# MM6108IQ_Chip.net
KiCad netlist of a schematic drawn in Altium Designer
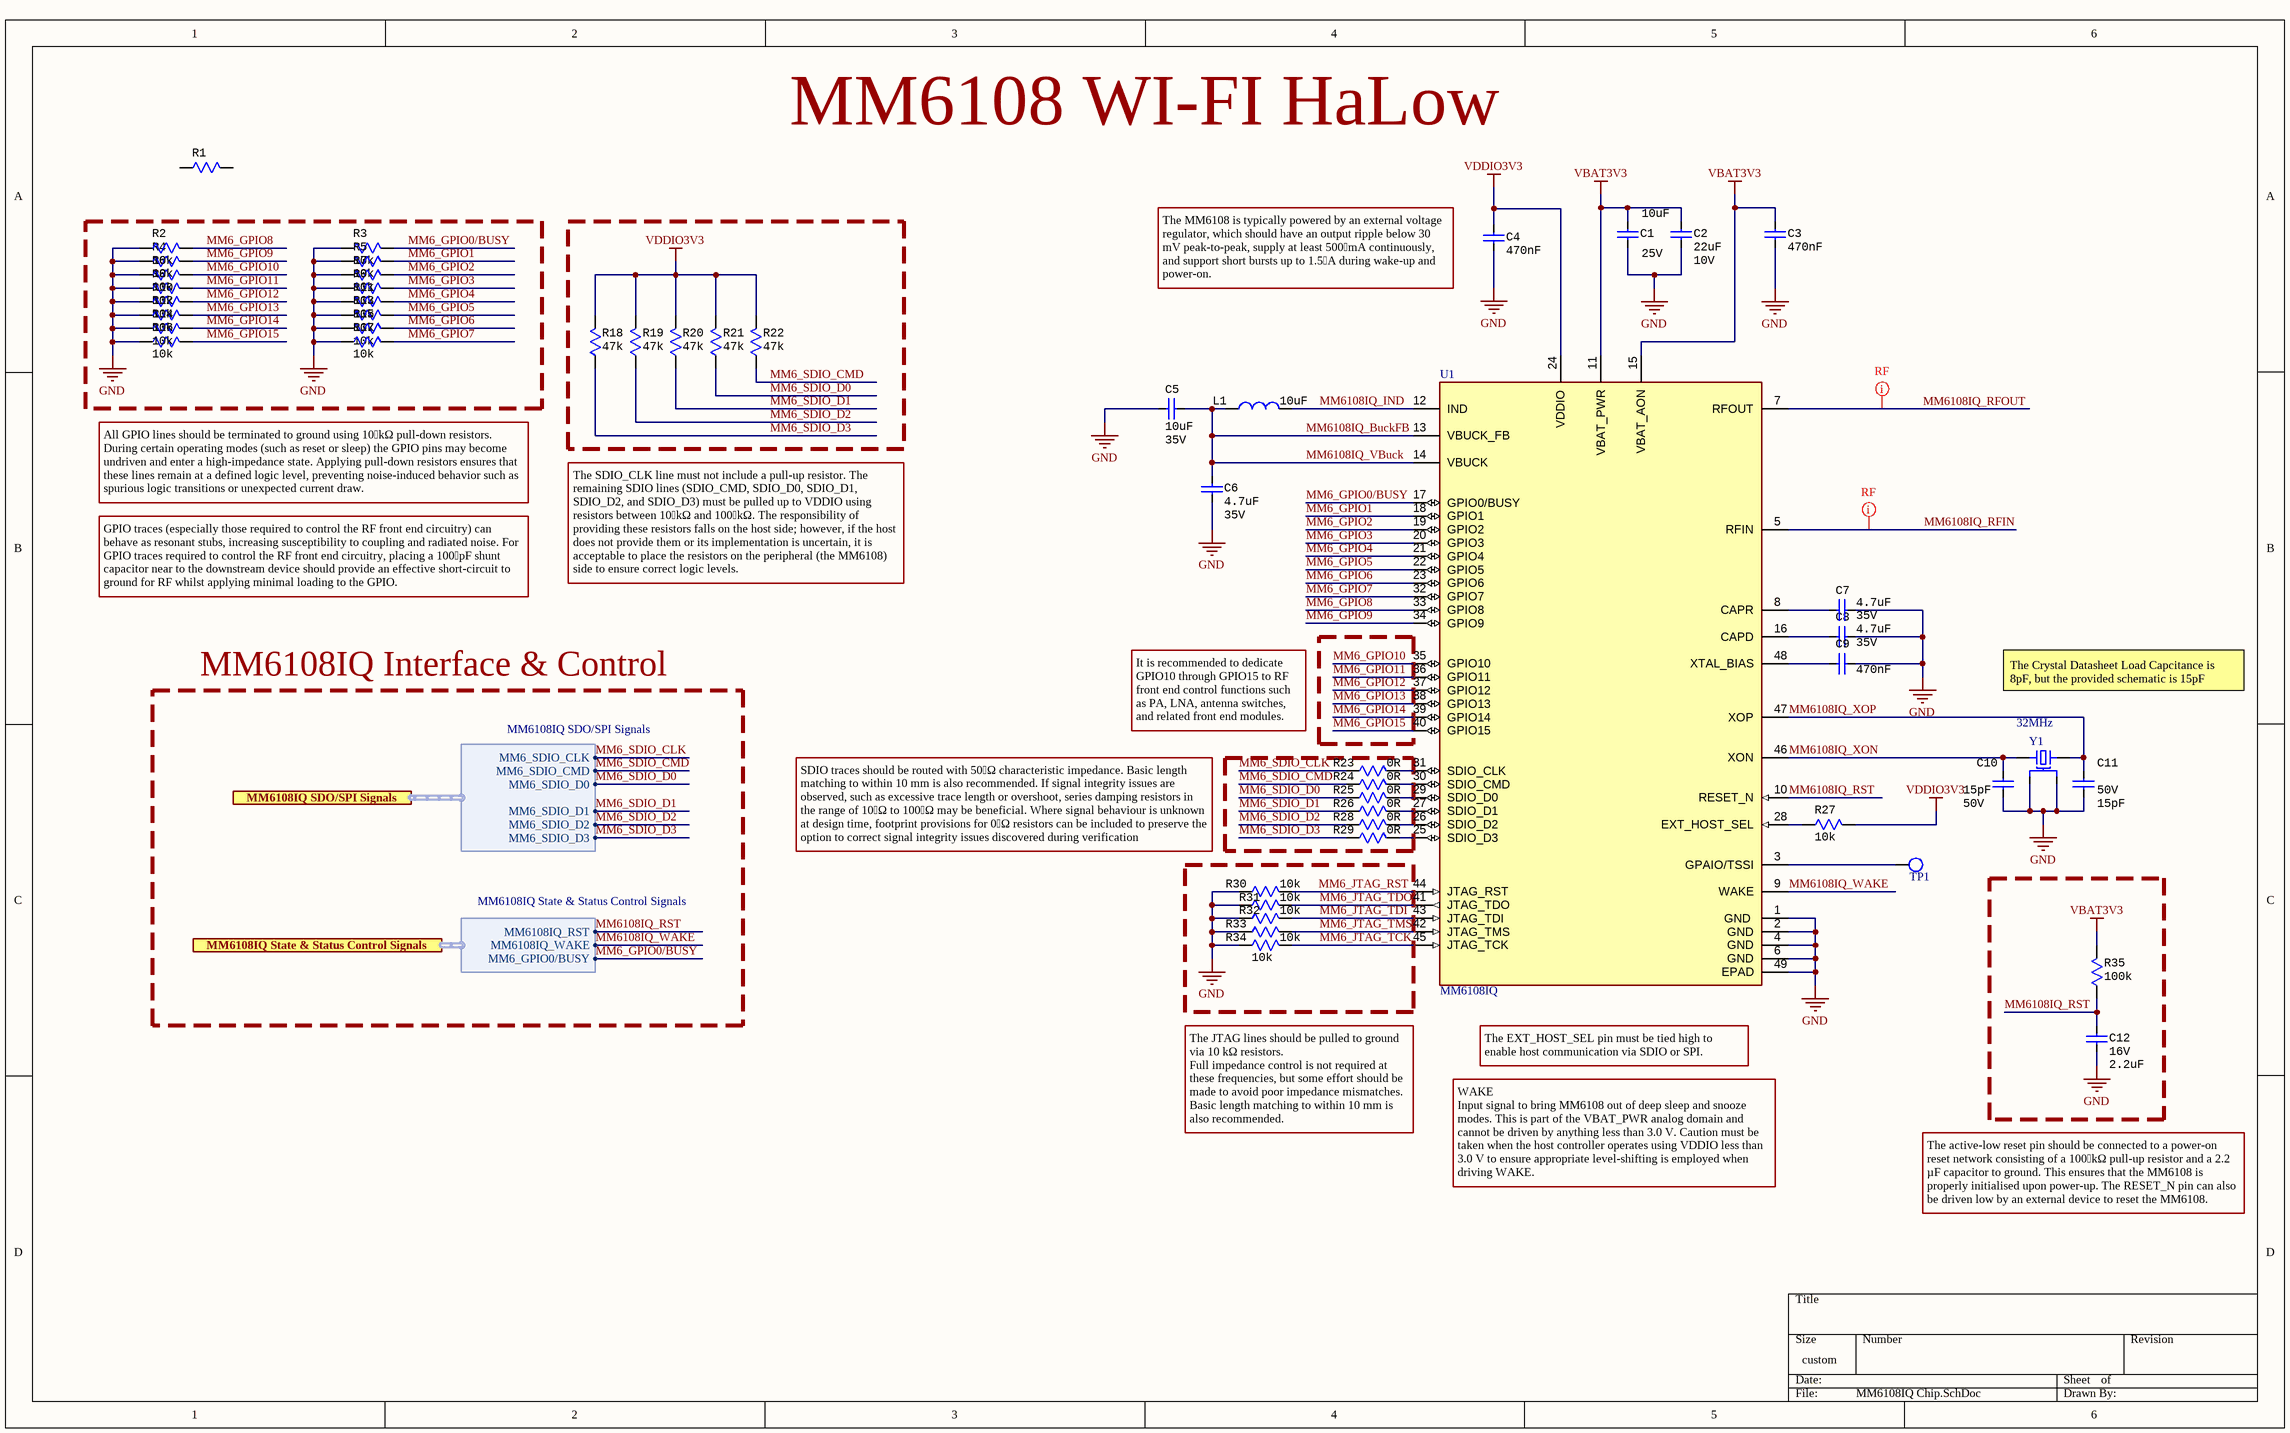
[diagram p0: MM6108IQ Chip.SchDoc]

(export (version "E")
  (design (tool "Eeschema 10.0.6"))
  (components
    (comp (ref "C1")
      (value "10uF")
      (footprint "CAP Ceramic SMD 0805")
      (description "CAP CER 10uF 25V X7R 0805")
      (fields
        (field (name "MANUFACTURER") "Samsung Electro-Mechanics")
        (field (name "MANUFACTURER PART NUMBER") "CL21B106KAYQNNE")
        (field (name "VOLTAGE") "25V")
      )
      (libsource (lib "MM6108IQ MotherBoard") (part "CAP 0805 10uF 25V 10%"))
    )
    (comp (ref "C2")
      (value "22uF")
      (footprint "CAP Ceramic SMD 0805")
      (description "CAP CER 22uF 10V X7R 0805")
      (fields
        (field (name "MANUFACTURER") "muRata")
        (field (name "MANUFACTURER PART NUMBER") "GRM21BZ71A226ME15L")
        (field (name "VOLTAGE") "10V")
      )
      (libsource (lib "MM6108IQ MotherBoard") (part "CAP 0805 22uF 10V"))
    )
    (comp (ref "C3")
      (value "470nF")
      (footprint "CAP Ceramic SMD 0603")
      (description "470nF ±10% 25V Ceramic Capacitor X7R 0603")
      (fields
        (field (name "MANUFACTURER") "Samsung Electro-Mechanics")
        (field (name "MANUFACTURER PART NUMBER") "CL10B474KA8NNNC")
      )
      (libsource (lib "MM6108IQ MotherBoard") (part "CAP 0603 470nF 25V"))
    )
    (comp (ref "C4")
      (value "470nF")
      (footprint "CAP Ceramic SMD 0603")
      (description "470nF ±10% 25V Ceramic Capacitor X7R 0603")
      (fields
        (field (name "MANUFACTURER") "Samsung Electro-Mechanics")
        (field (name "MANUFACTURER PART NUMBER") "CL10B474KA8NNNC")
      )
      (libsource (lib "MM6108IQ MotherBoard") (part "CAP 0603 470nF 25V"))
    )
    (comp (ref "C5")
      (value "10uF")
      (footprint "CAP Ceramic SMD 0603")
      (description "Cap Ceramic 10uF 35V X5R 20% Pad SMD 0603 85C T/R")
      (fields
        (field (name "MANUFACTURER") "Murata")
        (field (name "MANUFACTURER PART NUMBER") "GRM188R6YA106MA73D")
        (field (name "VOLTAGE") "35V")
      )
      (libsource (lib "MM6108IQ MotherBoard") (part "CAP 0603 10uF 35V"))
    )
    (comp (ref "C6")
      (value "4.7uF")
      (footprint "CAP Ceramic SMD 0603")
      (description "25V 4.7uF X5R ±10% 0603 Multilayer Ceramic Capacitors MLCC - SMD/SMT ROHS")
      (fields
        (field (name "MANUFACTURER") "Samsung Electro-Mechanics")
        (field (name "MANUFACTURER PART NUMBER") "CL10A475KA8NQNC")
        (field (name "VOLTAGE") "35V")
      )
      (libsource (lib "MM6108IQ MotherBoard") (part "CAP 0603 4.7uF 25V X5R 10%"))
    )
    (comp (ref "C7")
      (value "4.7uF")
      (footprint "CAP Ceramic SMD 0603")
      (description "25V 4.7uF X5R ±10% 0603 Multilayer Ceramic Capacitors MLCC - SMD/SMT ROHS")
      (fields
        (field (name "MANUFACTURER") "Samsung Electro-Mechanics")
        (field (name "MANUFACTURER PART NUMBER") "CL10A475KA8NQNC")
        (field (name "VOLTAGE") "35V")
      )
      (libsource (lib "MM6108IQ MotherBoard") (part "CAP 0603 4.7uF 25V X5R 10%"))
    )
    (comp (ref "C8")
      (value "4.7uF")
      (footprint "CAP Ceramic SMD 0603")
      (description "25V 4.7uF X5R ±10% 0603 Multilayer Ceramic Capacitors MLCC - SMD/SMT ROHS")
      (fields
        (field (name "MANUFACTURER") "Samsung Electro-Mechanics")
        (field (name "MANUFACTURER PART NUMBER") "CL10A475KA8NQNC")
        (field (name "VOLTAGE") "35V")
      )
      (libsource (lib "MM6108IQ MotherBoard") (part "CAP 0603 4.7uF 25V X5R 10%"))
    )
    (comp (ref "C9")
      (value "470nF")
      (footprint "CAP Ceramic SMD 0603")
      (description "470nF ±10% 25V Ceramic Capacitor X7R 0603")
      (fields
        (field (name "MANUFACTURER") "Samsung Electro-Mechanics")
        (field (name "MANUFACTURER PART NUMBER") "CL10B474KA8NNNC")
      )
      (libsource (lib "MM6108IQ MotherBoard") (part "CAP 0603 470nF 25V"))
    )
    (comp (ref "C10")
      (value "15pF")
      (footprint "CAP Ceramic SMD 0603")
      (description "50V 15pF NP0 ±5% 0603 Multilayer Ceramic Capacitors MLCC - SMD/SMT ROHS")
      (fields
        (field (name "MANUFACTURER") "Yageo")
        (field (name "MANUFACTURER PART NUMBER") "CC0603JRNPO9BN150")
        (field (name "VOLTAGE") "50V")
      )
      (libsource (lib "MM6108IQ MotherBoard") (part "CAP 0603 15pF 50V NP0 5%"))
    )
    (comp (ref "C11")
      (value "15pF")
      (footprint "CAP Ceramic SMD 0603")
      (description "50V 15pF NP0 ±5% 0603 Multilayer Ceramic Capacitors MLCC - SMD/SMT ROHS")
      (fields
        (field (name "MANUFACTURER") "Yageo")
        (field (name "MANUFACTURER PART NUMBER") "CC0603JRNPO9BN150")
        (field (name "VOLTAGE") "50V")
      )
      (libsource (lib "MM6108IQ MotherBoard") (part "CAP 0603 15pF 50V NP0 5%"))
    )
    (comp (ref "C12")
      (value "2.2uF")
      (footprint "CAP Ceramic SMD 0603")
      (description "16V 2.2uF X5R ±10% 0603 Multilayer Ceramic Capacitors MLCC - SMD/SMT ROHS")
      (fields
        (field (name "MANUFACTURER") "YAGEO")
        (field (name "MANUFACTURER PART NUMBER") "CC0603KRX5R7BB225")
        (field (name "VOLTAGE") "16V")
        (field (name "CAPACITANCE") "2.2uF")
      )
      (libsource (lib "MM6108IQ MotherBoard") (part "CAP 0603 2.2uF 16V"))
    )
    (comp (ref "L1")
      (value "10uF")
      (footprint "IND SMD 1210")
      (description "FIXED IND 10uH 2.2A 210mΩ 1210")
      (fields
        (field (name "MANUFACTURER") "XR")
        (field (name "MANUFACTURER PART NUMBER") "XRTC322512S100MBCA")
      )
      (libsource (lib "MM6108IQ MotherBoard") (part "IND 1210 10uF 20% 2.2A"))
    )
    (comp (ref "R1")
      (value "~")
      (footprint "RES SMD 0603")
      (description "100mW Thick Film Resistors 75V ±100ppm/℃ ±1% 10kΩ 0603 Chip Resistor - Surface Mount ROHS")
      (fields
        (field (name "MANUFACTURER") "YAGEO")
        (field (name "MANUFACTURER PART NUMBER") "RC0603FR-0710KL")
      )
      (libsource (lib "MM6108IQ MotherBoard") (part "RES 0603 10k 1%"))
    )
    (comp (ref "R2")
      (value "10k")
      (footprint "RES SMD 0603")
      (description "100mW Thick Film Resistors 75V ±100ppm/℃ ±1% 10kΩ 0603 Chip Resistor - Surface Mount ROHS")
      (fields
        (field (name "MANUFACTURER") "YAGEO")
        (field (name "MANUFACTURER PART NUMBER") "RC0603FR-0710KL")
      )
      (libsource (lib "MM6108IQ MotherBoard") (part "RES 0603 10k 1%"))
    )
    (comp (ref "R3")
      (value "10k")
      (footprint "RES SMD 0603")
      (description "100mW Thick Film Resistors 75V ±100ppm/℃ ±1% 10kΩ 0603 Chip Resistor - Surface Mount ROHS")
      (fields
        (field (name "MANUFACTURER") "YAGEO")
        (field (name "MANUFACTURER PART NUMBER") "RC0603FR-0710KL")
      )
      (libsource (lib "MM6108IQ MotherBoard") (part "RES 0603 10k 1%"))
    )
    (comp (ref "R4")
      (value "10k")
      (footprint "RES SMD 0603")
      (description "100mW Thick Film Resistors 75V ±100ppm/℃ ±1% 10kΩ 0603 Chip Resistor - Surface Mount ROHS")
      (fields
        (field (name "MANUFACTURER") "YAGEO")
        (field (name "MANUFACTURER PART NUMBER") "RC0603FR-0710KL")
      )
      (libsource (lib "MM6108IQ MotherBoard") (part "RES 0603 10k 1%"))
    )
    (comp (ref "R5")
      (value "10k")
      (footprint "RES SMD 0603")
      (description "100mW Thick Film Resistors 75V ±100ppm/℃ ±1% 10kΩ 0603 Chip Resistor - Surface Mount ROHS")
      (fields
        (field (name "MANUFACTURER") "YAGEO")
        (field (name "MANUFACTURER PART NUMBER") "RC0603FR-0710KL")
      )
      (libsource (lib "MM6108IQ MotherBoard") (part "RES 0603 10k 1%"))
    )
    (comp (ref "R6")
      (value "10k")
      (footprint "RES SMD 0603")
      (description "100mW Thick Film Resistors 75V ±100ppm/℃ ±1% 10kΩ 0603 Chip Resistor - Surface Mount ROHS")
      (fields
        (field (name "MANUFACTURER") "YAGEO")
        (field (name "MANUFACTURER PART NUMBER") "RC0603FR-0710KL")
      )
      (libsource (lib "MM6108IQ MotherBoard") (part "RES 0603 10k 1%"))
    )
    (comp (ref "R7")
      (value "10k")
      (footprint "RES SMD 0603")
      (description "100mW Thick Film Resistors 75V ±100ppm/℃ ±1% 10kΩ 0603 Chip Resistor - Surface Mount ROHS")
      (fields
        (field (name "MANUFACTURER") "YAGEO")
        (field (name "MANUFACTURER PART NUMBER") "RC0603FR-0710KL")
      )
      (libsource (lib "MM6108IQ MotherBoard") (part "RES 0603 10k 1%"))
    )
    (comp (ref "R8")
      (value "10k")
      (footprint "RES SMD 0603")
      (description "100mW Thick Film Resistors 75V ±100ppm/℃ ±1% 10kΩ 0603 Chip Resistor - Surface Mount ROHS")
      (fields
        (field (name "MANUFACTURER") "YAGEO")
        (field (name "MANUFACTURER PART NUMBER") "RC0603FR-0710KL")
      )
      (libsource (lib "MM6108IQ MotherBoard") (part "RES 0603 10k 1%"))
    )
    (comp (ref "R9")
      (value "10k")
      (footprint "RES SMD 0603")
      (description "100mW Thick Film Resistors 75V ±100ppm/℃ ±1% 10kΩ 0603 Chip Resistor - Surface Mount ROHS")
      (fields
        (field (name "MANUFACTURER") "YAGEO")
        (field (name "MANUFACTURER PART NUMBER") "RC0603FR-0710KL")
      )
      (libsource (lib "MM6108IQ MotherBoard") (part "RES 0603 10k 1%"))
    )
    (comp (ref "R10")
      (value "10k")
      (footprint "RES SMD 0603")
      (description "100mW Thick Film Resistors 75V ±100ppm/℃ ±1% 10kΩ 0603 Chip Resistor - Surface Mount ROHS")
      (fields
        (field (name "MANUFACTURER") "YAGEO")
        (field (name "MANUFACTURER PART NUMBER") "RC0603FR-0710KL")
      )
      (libsource (lib "MM6108IQ MotherBoard") (part "RES 0603 10k 1%"))
    )
    (comp (ref "R11")
      (value "10k")
      (footprint "RES SMD 0603")
      (description "100mW Thick Film Resistors 75V ±100ppm/℃ ±1% 10kΩ 0603 Chip Resistor - Surface Mount ROHS")
      (fields
        (field (name "MANUFACTURER") "YAGEO")
        (field (name "MANUFACTURER PART NUMBER") "RC0603FR-0710KL")
      )
      (libsource (lib "MM6108IQ MotherBoard") (part "RES 0603 10k 1%"))
    )
    (comp (ref "R12")
      (value "10k")
      (footprint "RES SMD 0603")
      (description "100mW Thick Film Resistors 75V ±100ppm/℃ ±1% 10kΩ 0603 Chip Resistor - Surface Mount ROHS")
      (fields
        (field (name "MANUFACTURER") "YAGEO")
        (field (name "MANUFACTURER PART NUMBER") "RC0603FR-0710KL")
      )
      (libsource (lib "MM6108IQ MotherBoard") (part "RES 0603 10k 1%"))
    )
    (comp (ref "R13")
      (value "10k")
      (footprint "RES SMD 0603")
      (description "100mW Thick Film Resistors 75V ±100ppm/℃ ±1% 10kΩ 0603 Chip Resistor - Surface Mount ROHS")
      (fields
        (field (name "MANUFACTURER") "YAGEO")
        (field (name "MANUFACTURER PART NUMBER") "RC0603FR-0710KL")
      )
      (libsource (lib "MM6108IQ MotherBoard") (part "RES 0603 10k 1%"))
    )
    (comp (ref "R14")
      (value "10k")
      (footprint "RES SMD 0603")
      (description "100mW Thick Film Resistors 75V ±100ppm/℃ ±1% 10kΩ 0603 Chip Resistor - Surface Mount ROHS")
      (fields
        (field (name "MANUFACTURER") "YAGEO")
        (field (name "MANUFACTURER PART NUMBER") "RC0603FR-0710KL")
      )
      (libsource (lib "MM6108IQ MotherBoard") (part "RES 0603 10k 1%"))
    )
    (comp (ref "R15")
      (value "10k")
      (footprint "RES SMD 0603")
      (description "100mW Thick Film Resistors 75V ±100ppm/℃ ±1% 10kΩ 0603 Chip Resistor - Surface Mount ROHS")
      (fields
        (field (name "MANUFACTURER") "YAGEO")
        (field (name "MANUFACTURER PART NUMBER") "RC0603FR-0710KL")
      )
      (libsource (lib "MM6108IQ MotherBoard") (part "RES 0603 10k 1%"))
    )
    (comp (ref "R16")
      (value "10k")
      (footprint "RES SMD 0603")
      (description "100mW Thick Film Resistors 75V ±100ppm/℃ ±1% 10kΩ 0603 Chip Resistor - Surface Mount ROHS")
      (fields
        (field (name "MANUFACTURER") "YAGEO")
        (field (name "MANUFACTURER PART NUMBER") "RC0603FR-0710KL")
      )
      (libsource (lib "MM6108IQ MotherBoard") (part "RES 0603 10k 1%"))
    )
    (comp (ref "R17")
      (value "10k")
      (footprint "RES SMD 0603")
      (description "100mW Thick Film Resistors 75V ±100ppm/℃ ±1% 10kΩ 0603 Chip Resistor - Surface Mount ROHS")
      (fields
        (field (name "MANUFACTURER") "YAGEO")
        (field (name "MANUFACTURER PART NUMBER") "RC0603FR-0710KL")
      )
      (libsource (lib "MM6108IQ MotherBoard") (part "RES 0603 10k 1%"))
    )
    (comp (ref "R18")
      (value "47k")
      (footprint "RES SMD 0603")
      (description "Res Thick Film 0603 47K Ohm 1% 1/10W ±100ppm/°C Molded SMD Punched Carrier T/R")
      (fields
        (field (name "MANUFACTURER") "YAGEO")
        (field (name "MANUFACTURER PART NUMBER") "RC0603FR-0747KL")
      )
      (libsource (lib "MM6108IQ MotherBoard") (part "RES 0603 47k 1%"))
    )
    (comp (ref "R19")
      (value "47k")
      (footprint "RES SMD 0603")
      (description "Res Thick Film 0603 47K Ohm 1% 1/10W ±100ppm/°C Molded SMD Punched Carrier T/R")
      (fields
        (field (name "MANUFACTURER") "YAGEO")
        (field (name "MANUFACTURER PART NUMBER") "RC0603FR-0747KL")
      )
      (libsource (lib "MM6108IQ MotherBoard") (part "RES 0603 47k 1%"))
    )
    (comp (ref "R20")
      (value "47k")
      (footprint "RES SMD 0603")
      (description "Res Thick Film 0603 47K Ohm 1% 1/10W ±100ppm/°C Molded SMD Punched Carrier T/R")
      (fields
        (field (name "MANUFACTURER") "YAGEO")
        (field (name "MANUFACTURER PART NUMBER") "RC0603FR-0747KL")
      )
      (libsource (lib "MM6108IQ MotherBoard") (part "RES 0603 47k 1%"))
    )
    (comp (ref "R21")
      (value "47k")
      (footprint "RES SMD 0603")
      (description "Res Thick Film 0603 47K Ohm 1% 1/10W ±100ppm/°C Molded SMD Punched Carrier T/R")
      (fields
        (field (name "MANUFACTURER") "YAGEO")
        (field (name "MANUFACTURER PART NUMBER") "RC0603FR-0747KL")
      )
      (libsource (lib "MM6108IQ MotherBoard") (part "RES 0603 47k 1%"))
    )
    (comp (ref "R22")
      (value "47k")
      (footprint "RES SMD 0603")
      (description "Res Thick Film 0603 47K Ohm 1% 1/10W ±100ppm/°C Molded SMD Punched Carrier T/R")
      (fields
        (field (name "MANUFACTURER") "YAGEO")
        (field (name "MANUFACTURER PART NUMBER") "RC0603FR-0747KL")
      )
      (libsource (lib "MM6108IQ MotherBoard") (part "RES 0603 47k 1%"))
    )
    (comp (ref "R23")
      (value "0R")
      (footprint "RES SMD 0603")
      (description "100mW Thick Film Resistors 75V ±5% 0Ω 0603 Chip Resistor - Surface Mount ROHS")
      (fields
        (field (name "MANUFACTURER") "YAGEO")
        (field (name "MANUFACTURER PART NUMBER") "RC0603JR-070RL")
      )
      (libsource (lib "MM6108IQ MotherBoard") (part "RES 0603 0R 1%"))
    )
    (comp (ref "R24")
      (value "0R")
      (footprint "RES SMD 0603")
      (description "100mW Thick Film Resistors 75V ±5% 0Ω 0603 Chip Resistor - Surface Mount ROHS")
      (fields
        (field (name "MANUFACTURER") "YAGEO")
        (field (name "MANUFACTURER PART NUMBER") "RC0603JR-070RL")
      )
      (libsource (lib "MM6108IQ MotherBoard") (part "RES 0603 0R 1%"))
    )
    (comp (ref "R25")
      (value "0R")
      (footprint "RES SMD 0603")
      (description "100mW Thick Film Resistors 75V ±5% 0Ω 0603 Chip Resistor - Surface Mount ROHS")
      (fields
        (field (name "MANUFACTURER") "YAGEO")
        (field (name "MANUFACTURER PART NUMBER") "RC0603JR-070RL")
      )
      (libsource (lib "MM6108IQ MotherBoard") (part "RES 0603 0R 1%"))
    )
    (comp (ref "R26")
      (value "0R")
      (footprint "RES SMD 0603")
      (description "100mW Thick Film Resistors 75V ±5% 0Ω 0603 Chip Resistor - Surface Mount ROHS")
      (fields
        (field (name "MANUFACTURER") "YAGEO")
        (field (name "MANUFACTURER PART NUMBER") "RC0603JR-070RL")
      )
      (libsource (lib "MM6108IQ MotherBoard") (part "RES 0603 0R 1%"))
    )
    (comp (ref "R27")
      (value "10k")
      (footprint "RES SMD 0603")
      (description "100mW Thick Film Resistors 75V ±100ppm/℃ ±1% 10kΩ 0603 Chip Resistor - Surface Mount ROHS")
      (fields
        (field (name "MANUFACTURER") "YAGEO")
        (field (name "MANUFACTURER PART NUMBER") "RC0603FR-0710KL")
      )
      (libsource (lib "MM6108IQ MotherBoard") (part "RES 0603 10k 1%"))
    )
    (comp (ref "R28")
      (value "0R")
      (footprint "RES SMD 0603")
      (description "100mW Thick Film Resistors 75V ±5% 0Ω 0603 Chip Resistor - Surface Mount ROHS")
      (fields
        (field (name "MANUFACTURER") "YAGEO")
        (field (name "MANUFACTURER PART NUMBER") "RC0603JR-070RL")
      )
      (libsource (lib "MM6108IQ MotherBoard") (part "RES 0603 0R 1%"))
    )
    (comp (ref "R29")
      (value "0R")
      (footprint "RES SMD 0603")
      (description "100mW Thick Film Resistors 75V ±5% 0Ω 0603 Chip Resistor - Surface Mount ROHS")
      (fields
        (field (name "MANUFACTURER") "YAGEO")
        (field (name "MANUFACTURER PART NUMBER") "RC0603JR-070RL")
      )
      (libsource (lib "MM6108IQ MotherBoard") (part "RES 0603 0R 1%"))
    )
    (comp (ref "R30")
      (value "10k")
      (footprint "RES SMD 0603")
      (description "100mW Thick Film Resistors 75V ±100ppm/℃ ±1% 10kΩ 0603 Chip Resistor - Surface Mount ROHS")
      (fields
        (field (name "MANUFACTURER") "YAGEO")
        (field (name "MANUFACTURER PART NUMBER") "RC0603FR-0710KL")
      )
      (libsource (lib "MM6108IQ MotherBoard") (part "RES 0603 10k 1%"))
    )
    (comp (ref "R31")
      (value "10k")
      (footprint "RES SMD 0603")
      (description "100mW Thick Film Resistors 75V ±100ppm/℃ ±1% 10kΩ 0603 Chip Resistor - Surface Mount ROHS")
      (fields
        (field (name "MANUFACTURER") "YAGEO")
        (field (name "MANUFACTURER PART NUMBER") "RC0603FR-0710KL")
      )
      (libsource (lib "MM6108IQ MotherBoard") (part "RES 0603 10k 1%"))
    )
    (comp (ref "R32")
      (value "10k")
      (footprint "RES SMD 0603")
      (description "100mW Thick Film Resistors 75V ±100ppm/℃ ±1% 10kΩ 0603 Chip Resistor - Surface Mount ROHS")
      (fields
        (field (name "MANUFACTURER") "YAGEO")
        (field (name "MANUFACTURER PART NUMBER") "RC0603FR-0710KL")
      )
      (libsource (lib "MM6108IQ MotherBoard") (part "RES 0603 10k 1%"))
    )
    (comp (ref "R33")
      (value "10k")
      (footprint "RES SMD 0603")
      (description "100mW Thick Film Resistors 75V ±100ppm/℃ ±1% 10kΩ 0603 Chip Resistor - Surface Mount ROHS")
      (fields
        (field (name "MANUFACTURER") "YAGEO")
        (field (name "MANUFACTURER PART NUMBER") "RC0603FR-0710KL")
      )
      (libsource (lib "MM6108IQ MotherBoard") (part "RES 0603 10k 1%"))
    )
    (comp (ref "R34")
      (value "10k")
      (footprint "RES SMD 0603")
      (description "100mW Thick Film Resistors 75V ±100ppm/℃ ±1% 10kΩ 0603 Chip Resistor - Surface Mount ROHS")
      (fields
        (field (name "MANUFACTURER") "YAGEO")
        (field (name "MANUFACTURER PART NUMBER") "RC0603FR-0710KL")
      )
      (libsource (lib "MM6108IQ MotherBoard") (part "RES 0603 10k 1%"))
    )
    (comp (ref "R35")
      (value "100k")
      (footprint "RES SMD 0603")
      (description "100mW Thick Film Resistors 75V ±100ppm/℃ ±1% 100kΩ 0603 Chip Resistor - Surface Mount ROHS")
      (fields
        (field (name "MANUFACTURER") "YAGEO")
        (field (name "MANUFACTURER PART NUMBER") "RC0603FR-07100KL")
      )
      (libsource (lib "MM6108IQ MotherBoard") (part "RES 0603 100k 1%"))
    )
    (comp (ref "TP1")
      (value "TestPoint")
      (footprint "TestPoint Surface 0.8mm")
      (libsource (lib "MM6108IQ MotherBoard") (part "TestPoint"))
    )
    (comp (ref "U1")
      (value "MM6108IQ")
      (footprint "QFN48 6x6")
      (fields (field (name "MANUFACTURER") "Morse Micro"))
      (libsource (lib "Communictation ICs") (part "MM6108IQ"))
    )
    (comp (ref "Y1")
      (value "32MHz")
      (footprint "XTAL_ECS-160-9-37-CKM-TR")
      (description "CRYSTAL 32MHz 8pF SMD")
      (fields
        (field (name "MANUFACTURER") "ECS")
        (field (name "MANUFACTURER PART NUMBER") "ECS-320-8-37B-CKY-TR")
      )
      (libsource (lib "MM6108IQ MotherBoard") (part "ECS-320-8-37B-CKY-TR"))
    )
  )
  (nets
    (net (code "8") (name "/MM6_GPIO0{slash}BUSY") (class "Default")
      (node (ref "R3") (pin "2") (pinfunction "2_2") (pintype "passive"))
      (node (ref "U1") (pin "17") (pinfunction "GPIO0/BUSY_17") (pintype "bidirectional"))
    )
    (net (code "9") (name "/MM6_GPIO1") (class "Default")
      (node (ref "R5") (pin "2") (pinfunction "2_2") (pintype "passive"))
      (node (ref "U1") (pin "18") (pinfunction "GPIO1_18") (pintype "bidirectional"))
    )
    (net (code "10") (name "/MM6_GPIO2") (class "Default")
      (node (ref "R7") (pin "2") (pinfunction "2_2") (pintype "passive"))
      (node (ref "U1") (pin "19") (pinfunction "GPIO2_19") (pintype "bidirectional"))
    )
    (net (code "11") (name "/MM6_GPIO3") (class "Default")
      (node (ref "R9") (pin "2") (pinfunction "2_2") (pintype "passive"))
      (node (ref "U1") (pin "20") (pinfunction "GPIO3_20") (pintype "bidirectional"))
    )
    (net (code "12") (name "/MM6_GPIO4") (class "Default")
      (node (ref "R11") (pin "2") (pinfunction "2_2") (pintype "passive"))
      (node (ref "U1") (pin "21") (pinfunction "GPIO4_21") (pintype "bidirectional"))
    )
    (net (code "13") (name "/MM6_GPIO5") (class "Default")
      (node (ref "R13") (pin "2") (pinfunction "2_2") (pintype "passive"))
      (node (ref "U1") (pin "22") (pinfunction "GPIO5_22") (pintype "bidirectional"))
    )
    (net (code "14") (name "/MM6_GPIO6") (class "Default")
      (node (ref "R15") (pin "2") (pinfunction "2_2") (pintype "passive"))
      (node (ref "U1") (pin "23") (pinfunction "GPIO6_23") (pintype "bidirectional"))
    )
    (net (code "15") (name "/MM6_GPIO7") (class "Default")
      (node (ref "R17") (pin "2") (pinfunction "2_2") (pintype "passive"))
      (node (ref "U1") (pin "32") (pinfunction "GPIO7_32") (pintype "bidirectional"))
    )
    (net (code "16") (name "/MM6_GPIO8") (class "Default")
      (node (ref "R2") (pin "2") (pinfunction "2_2") (pintype "passive"))
      (node (ref "U1") (pin "33") (pinfunction "GPIO8_33") (pintype "bidirectional"))
    )
    (net (code "17") (name "/MM6_GPIO9") (class "Default")
      (node (ref "R4") (pin "2") (pinfunction "2_2") (pintype "passive"))
      (node (ref "U1") (pin "34") (pinfunction "GPIO9_34") (pintype "bidirectional"))
    )
    (net (code "18") (name "/MM6_GPIO10") (class "Default")
      (node (ref "R6") (pin "2") (pinfunction "2_2") (pintype "passive"))
      (node (ref "U1") (pin "35") (pinfunction "GPIO10_35") (pintype "bidirectional"))
    )
    (net (code "19") (name "/MM6_GPIO11") (class "Default")
      (node (ref "R8") (pin "2") (pinfunction "2_2") (pintype "passive"))
      (node (ref "U1") (pin "36") (pinfunction "GPIO11_36") (pintype "bidirectional"))
    )
    (net (code "20") (name "/MM6_GPIO12") (class "Default")
      (node (ref "R10") (pin "2") (pinfunction "2_2") (pintype "passive"))
      (node (ref "U1") (pin "37") (pinfunction "GPIO12_37") (pintype "bidirectional"))
    )
    (net (code "21") (name "/MM6_GPIO13") (class "Default")
      (node (ref "R12") (pin "2") (pinfunction "2_2") (pintype "passive"))
      (node (ref "U1") (pin "38") (pinfunction "GPIO13_38") (pintype "bidirectional"))
    )
    (net (code "22") (name "/MM6_GPIO14") (class "Default")
      (node (ref "R14") (pin "2") (pinfunction "2_2") (pintype "passive"))
      (node (ref "U1") (pin "39") (pinfunction "GPIO14_39") (pintype "bidirectional"))
    )
    (net (code "23") (name "/MM6_GPIO15") (class "Default")
      (node (ref "R16") (pin "2") (pinfunction "2_2") (pintype "passive"))
      (node (ref "U1") (pin "40") (pinfunction "GPIO15_40") (pintype "bidirectional"))
    )
    (net (code "24") (name "/MM6_JTAG_RST") (class "Default")
      (node (ref "R30") (pin "2") (pinfunction "2_2") (pintype "passive"))
      (node (ref "U1") (pin "44") (pinfunction "JTAG_RST_44") (pintype "input"))
    )
    (net (code "25") (name "/MM6_JTAG_TCK") (class "Default")
      (node (ref "R34") (pin "2") (pinfunction "2_2") (pintype "passive"))
      (node (ref "U1") (pin "45") (pinfunction "JTAG_TCK_45") (pintype "input"))
    )
    (net (code "26") (name "/MM6_JTAG_TDI") (class "Default")
      (node (ref "R32") (pin "2") (pinfunction "2_2") (pintype "passive"))
      (node (ref "U1") (pin "43") (pinfunction "JTAG_TDI_43") (pintype "input"))
    )
    (net (code "27") (name "/MM6_JTAG_TDO") (class "Default")
      (node (ref "R31") (pin "2") (pinfunction "2_2") (pintype "passive"))
      (node (ref "U1") (pin "41") (pinfunction "JTAG_TDO_41") (pintype "output"))
    )
    (net (code "28") (name "/MM6_JTAG_TMS") (class "Default")
      (node (ref "R33") (pin "2") (pinfunction "2_2") (pintype "passive"))
      (node (ref "U1") (pin "42") (pinfunction "JTAG_TMS_42") (pintype "input"))
    )
    (net (code "29") (name "/MM6_SDIO_CLK") (class "Default")
      (node (ref "R23") (pin "1") (pinfunction "1_1") (pintype "passive"))
    )
    (net (code "30") (name "/MM6_SDIO_CMD") (class "Default")
      (node (ref "R22") (pin "1") (pinfunction "1_1") (pintype "passive"))
      (node (ref "R24") (pin "1") (pinfunction "1_1") (pintype "passive"))
    )
    (net (code "31") (name "/MM6_SDIO_D0") (class "Default")
      (node (ref "R21") (pin "1") (pinfunction "1_1") (pintype "passive"))
      (node (ref "R25") (pin "1") (pinfunction "1_1") (pintype "passive"))
    )
    (net (code "32") (name "/MM6_SDIO_D1") (class "Default")
      (node (ref "R20") (pin "1") (pinfunction "1_1") (pintype "passive"))
      (node (ref "R26") (pin "1") (pinfunction "1_1") (pintype "passive"))
    )
    (net (code "33") (name "/MM6_SDIO_D2") (class "Default")
      (node (ref "R19") (pin "1") (pinfunction "1_1") (pintype "passive"))
      (node (ref "R28") (pin "1") (pinfunction "1_1") (pintype "passive"))
    )
    (net (code "34") (name "/MM6_SDIO_D3") (class "Default")
      (node (ref "R18") (pin "1") (pinfunction "1_1") (pintype "passive"))
      (node (ref "R29") (pin "1") (pinfunction "1_1") (pintype "passive"))
    )
    (net (code "35") (name "/MM6108IQ_BuckFB") (class "Default")
      (node (ref "C5") (pin "2") (pinfunction "2_2") (pintype "passive"))
      (node (ref "C6") (pin "1") (pinfunction "1_1") (pintype "passive"))
      (node (ref "L1") (pin "2") (pinfunction "2_2") (pintype "passive"))
      (node (ref "U1") (pin "13") (pinfunction "VBUCK_FB_13") (pintype "power_in"))
      (node (ref "U1") (pin "14") (pinfunction "VBUCK_14") (pintype "power_in"))
    )
    (net (code "36") (name "/MM6108IQ_IND") (class "Default")
      (node (ref "L1") (pin "1") (pinfunction "1_1") (pintype "passive"))
      (node (ref "U1") (pin "12") (pinfunction "IND_12") (pintype "passive"))
    )
    (net (code "37") (name "/MM6108IQ_RFIN") (class "Default")
      (node (ref "U1") (pin "5") (pinfunction "RFIN_5") (pintype "passive"))
    )
    (net (code "38") (name "/MM6108IQ_RFOUT") (class "Default")
      (node (ref "U1") (pin "7") (pinfunction "RFOUT_7") (pintype "passive"))
    )
    (net (code "39") (name "/MM6108IQ_RST") (class "Default")
      (node (ref "C12") (pin "1") (pinfunction "1_1") (pintype "passive"))
      (node (ref "R35") (pin "1") (pinfunction "1_1") (pintype "passive"))
      (node (ref "U1") (pin "10") (pinfunction "RESET_N_10") (pintype "input"))
    )
    (net (code "40") (name "/MM6108IQ_WAKE") (class "Default")
      (node (ref "U1") (pin "9") (pinfunction "WAKE_9") (pintype "passive"))
    )
    (net (code "41") (name "/MM6108IQ_XON") (class "Default")
      (node (ref "C10") (pin "1") (pinfunction "1_1") (pintype "passive"))
      (node (ref "U1") (pin "46") (pinfunction "XON_46") (pintype "passive"))
      (node (ref "Y1") (pin "1") (pinfunction "1_1") (pintype "passive"))
    )
    (net (code "42") (name "/MM6108IQ_XOP") (class "Default")
      (node (ref "C11") (pin "1") (pinfunction "1_1") (pintype "passive"))
      (node (ref "U1") (pin "47") (pinfunction "XOP_47") (pintype "passive"))
      (node (ref "Y1") (pin "3") (pinfunction "3_3") (pintype "passive"))
    )
    (net (code "45") (name "GND") (class "Default")
      (node (ref "C1") (pin "2") (pinfunction "2_2") (pintype "passive"))
      (node (ref "C10") (pin "2") (pinfunction "2_2") (pintype "passive"))
      (node (ref "C11") (pin "2") (pinfunction "2_2") (pintype "passive"))
      (node (ref "C12") (pin "2") (pinfunction "2_2") (pintype "passive"))
      (node (ref "C2") (pin "2") (pinfunction "2_2") (pintype "passive"))
      (node (ref "C3") (pin "2") (pinfunction "2_2") (pintype "passive"))
      (node (ref "C4") (pin "1") (pinfunction "1_1") (pintype "passive"))
      (node (ref "C5") (pin "1") (pinfunction "1_1") (pintype "passive"))
      (node (ref "C6") (pin "2") (pinfunction "2_2") (pintype "passive"))
      (node (ref "C7") (pin "2") (pinfunction "2_2") (pintype "passive"))
      (node (ref "C8") (pin "2") (pinfunction "2_2") (pintype "passive"))
      (node (ref "C9") (pin "2") (pinfunction "2_2") (pintype "passive"))
      (node (ref "R10") (pin "1") (pinfunction "1_1") (pintype "passive"))
      (node (ref "R11") (pin "1") (pinfunction "1_1") (pintype "passive"))
      (node (ref "R12") (pin "1") (pinfunction "1_1") (pintype "passive"))
      (node (ref "R13") (pin "1") (pinfunction "1_1") (pintype "passive"))
      (node (ref "R14") (pin "1") (pinfunction "1_1") (pintype "passive"))
      (node (ref "R15") (pin "1") (pinfunction "1_1") (pintype "passive"))
      (node (ref "R16") (pin "1") (pinfunction "1_1") (pintype "passive"))
      (node (ref "R17") (pin "1") (pinfunction "1_1") (pintype "passive"))
      (node (ref "R2") (pin "1") (pinfunction "1_1") (pintype "passive"))
      (node (ref "R3") (pin "1") (pinfunction "1_1") (pintype "passive"))
      (node (ref "R30") (pin "1") (pinfunction "1_1") (pintype "passive"))
      (node (ref "R31") (pin "1") (pinfunction "1_1") (pintype "passive"))
      (node (ref "R32") (pin "1") (pinfunction "1_1") (pintype "passive"))
      (node (ref "R33") (pin "1") (pinfunction "1_1") (pintype "passive"))
      (node (ref "R34") (pin "1") (pinfunction "1_1") (pintype "passive"))
      (node (ref "R4") (pin "1") (pinfunction "1_1") (pintype "passive"))
      (node (ref "R5") (pin "1") (pinfunction "1_1") (pintype "passive"))
      (node (ref "R6") (pin "1") (pinfunction "1_1") (pintype "passive"))
      (node (ref "R7") (pin "1") (pinfunction "1_1") (pintype "passive"))
      (node (ref "R8") (pin "1") (pinfunction "1_1") (pintype "passive"))
      (node (ref "R9") (pin "1") (pinfunction "1_1") (pintype "passive"))
      (node (ref "U1") (pin "1") (pinfunction "GND_1") (pintype "passive"))
      (node (ref "U1") (pin "2") (pinfunction "GND_2") (pintype "passive"))
      (node (ref "U1") (pin "4") (pinfunction "GND_4") (pintype "power_in"))
      (node (ref "U1") (pin "49") (pinfunction "EPAD_49") (pintype "power_in"))
      (node (ref "U1") (pin "6") (pinfunction "GND_6") (pintype "power_in"))
      (node (ref "Y1") (pin "2") (pinfunction "NC_2") (pintype "passive"))
      (node (ref "Y1") (pin "4") (pinfunction "4_4") (pintype "passive"))
    )
    (net (code "46") (name "Net-(U1-CAPD)") (class "Default")
      (node (ref "C8") (pin "1") (pinfunction "1_1") (pintype "passive"))
      (node (ref "U1") (pin "16") (pinfunction "CAPD_16") (pintype "power_in"))
    )
    (net (code "47") (name "Net-(U1-CAPR)") (class "Default")
      (node (ref "C7") (pin "1") (pinfunction "1_1") (pintype "passive"))
      (node (ref "U1") (pin "8") (pinfunction "CAPR_8") (pintype "power_in"))
    )
    (net (code "48") (name "Net-(U1-EXT_HOST_SEL)") (class "Default")
      (node (ref "R27") (pin "1") (pinfunction "1_1") (pintype "passive"))
      (node (ref "U1") (pin "28") (pinfunction "EXT_HOST_SEL_28") (pintype "input"))
    )
    (net (code "49") (name "Net-(U1-GPAIO{slash}TSSI)") (class "Default")
      (node (ref "TP1") (pin "1") (pinfunction "1_1") (pintype "passive"))
      (node (ref "U1") (pin "3") (pinfunction "GPAIO/TSSI_3") (pintype "passive"))
    )
    (net (code "50") (name "Net-(U1-SDIO_CLK)") (class "Default")
      (node (ref "R23") (pin "2") (pinfunction "2_2") (pintype "passive"))
      (node (ref "U1") (pin "31") (pinfunction "SDIO_CLK_31") (pintype "bidirectional"))
    )
    (net (code "51") (name "Net-(U1-SDIO_CMD)") (class "Default")
      (node (ref "R24") (pin "2") (pinfunction "2_2") (pintype "passive"))
      (node (ref "U1") (pin "30") (pinfunction "SDIO_CMD_30") (pintype "bidirectional"))
    )
    (net (code "52") (name "Net-(U1-SDIO_D0)") (class "Default")
      (node (ref "R25") (pin "2") (pinfunction "2_2") (pintype "passive"))
      (node (ref "U1") (pin "29") (pinfunction "SDIO_D0_29") (pintype "bidirectional"))
    )
    (net (code "53") (name "Net-(U1-SDIO_D1)") (class "Default")
      (node (ref "R26") (pin "2") (pinfunction "2_2") (pintype "passive"))
      (node (ref "U1") (pin "27") (pinfunction "SDIO_D1_27") (pintype "bidirectional"))
    )
    (net (code "54") (name "Net-(U1-SDIO_D2)") (class "Default")
      (node (ref "R28") (pin "2") (pinfunction "2_2") (pintype "passive"))
      (node (ref "U1") (pin "26") (pinfunction "SDIO_D2_26") (pintype "bidirectional"))
    )
    (net (code "55") (name "Net-(U1-SDIO_D3)") (class "Default")
      (node (ref "R29") (pin "2") (pinfunction "2_2") (pintype "passive"))
      (node (ref "U1") (pin "25") (pinfunction "SDIO_D3_25") (pintype "bidirectional"))
    )
    (net (code "56") (name "Net-(U1-XTAL_BIAS)") (class "Default")
      (node (ref "C9") (pin "1") (pinfunction "1_1") (pintype "passive"))
      (node (ref "U1") (pin "48") (pinfunction "XTAL_BIAS_48") (pintype "passive"))
    )
    (net (code "57") (name "VBAT3V3") (class "Default")
      (node (ref "C1") (pin "1") (pinfunction "1_1") (pintype "passive"))
      (node (ref "C2") (pin "1") (pinfunction "1_1") (pintype "passive"))
      (node (ref "C3") (pin "1") (pinfunction "1_1") (pintype "passive"))
      (node (ref "R35") (pin "2") (pinfunction "2_2") (pintype "passive"))
      (node (ref "U1") (pin "11") (pinfunction "VBAT_PWR_11") (pintype "power_in"))
      (node (ref "U1") (pin "15") (pinfunction "VBAT_AON_15") (pintype "power_in"))
    )
    (net (code "58") (name "VDDIO3V3") (class "Default")
      (node (ref "C4") (pin "2") (pinfunction "2_2") (pintype "passive"))
      (node (ref "R18") (pin "2") (pinfunction "2_2") (pintype "passive"))
      (node (ref "R19") (pin "2") (pinfunction "2_2") (pintype "passive"))
      (node (ref "R20") (pin "2") (pinfunction "2_2") (pintype "passive"))
      (node (ref "R21") (pin "2") (pinfunction "2_2") (pintype "passive"))
      (node (ref "R22") (pin "2") (pinfunction "2_2") (pintype "passive"))
      (node (ref "R27") (pin "2") (pinfunction "2_2") (pintype "passive"))
      (node (ref "U1") (pin "24") (pinfunction "VDDIO_24") (pintype "power_in"))
    )
    (net (code "59") (name "unconnected-(R1-Pad1)") (class "Default")
      (node (ref "R1") (pin "1") (pinfunction "1_1") (pintype "passive"))
    )
    (net (code "60") (name "unconnected-(R1-Pad2)") (class "Default")
      (node (ref "R1") (pin "2") (pinfunction "2_2") (pintype "passive"))
    )
  )
)
